# NeoSevenSegment.net
KiCad netlist of a schematic drawn in EAGLE
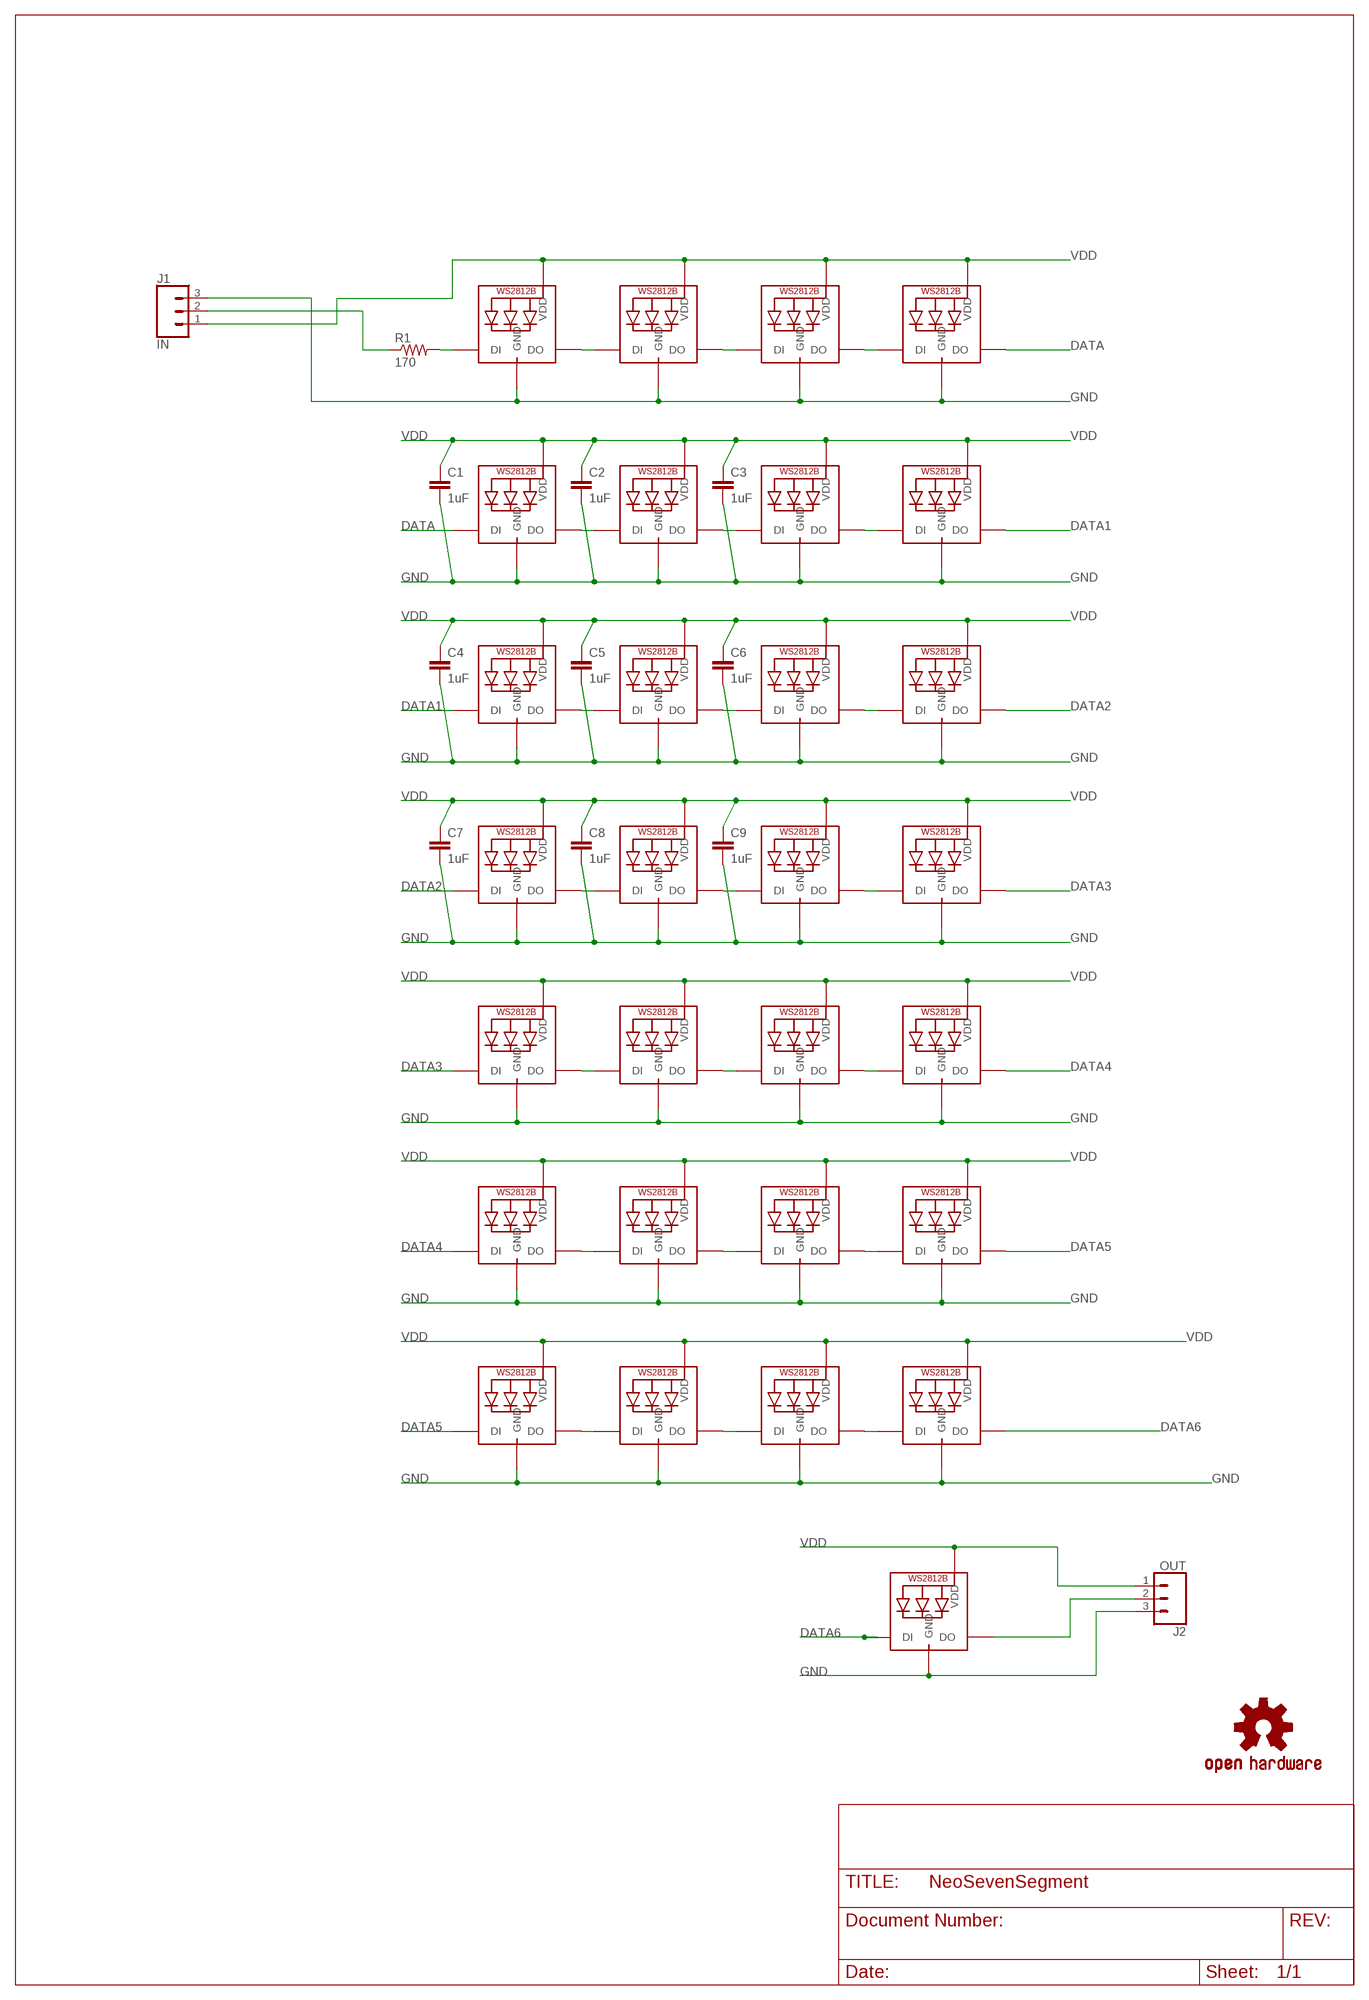
[diagram p0: schematic, sheet 1]

(export (version "E")
  (design (tool "Eeschema 10.0.6"))
  (components
    (comp (ref "C1")
      (value "1uF")
      (footprint "eagle-import:C1210")
      (libsource (lib "eagle-import") (part "C-EUC1210"))
    )
    (comp (ref "C2")
      (value "1uF")
      (footprint "eagle-import:C1210")
      (libsource (lib "eagle-import") (part "C-EUC1210"))
    )
    (comp (ref "C3")
      (value "1uF")
      (footprint "eagle-import:C1210")
      (libsource (lib "eagle-import") (part "C-EUC1210"))
    )
    (comp (ref "C4")
      (value "1uF")
      (footprint "eagle-import:C1210")
      (libsource (lib "eagle-import") (part "C-EUC1210"))
    )
    (comp (ref "C5")
      (value "1uF")
      (footprint "eagle-import:C1210")
      (libsource (lib "eagle-import") (part "C-EUC1210"))
    )
    (comp (ref "C6")
      (value "1uF")
      (footprint "eagle-import:C1210")
      (libsource (lib "eagle-import") (part "C-EUC1210"))
    )
    (comp (ref "C7")
      (value "1uF")
      (footprint "eagle-import:C1210")
      (libsource (lib "eagle-import") (part "C-EUC1210"))
    )
    (comp (ref "C8")
      (value "1uF")
      (footprint "eagle-import:C1210")
      (libsource (lib "eagle-import") (part "C-EUC1210"))
    )
    (comp (ref "C9")
      (value "1uF")
      (footprint "eagle-import:C1210")
      (libsource (lib "eagle-import") (part "C-EUC1210"))
    )
    (comp (ref "J1")
      (value "IN")
      (footprint "eagle-import:1X03_LONGPADS")
      (libsource (lib "eagle-import") (part "CONN_03LONGPADS"))
    )
    (comp (ref "J2")
      (value "OUT")
      (footprint "eagle-import:1X03_LONGPADS")
      (libsource (lib "eagle-import") (part "CONN_03LONGPADS"))
    )
    (comp (ref "LED1")
      (value "WS2812B_5050N")
      (footprint "eagle-import:WS2812B-NARROW")
      (libsource (lib "eagle-import") (part "WS2812B_5050N"))
    )
    (comp (ref "LED2")
      (value "WS2812B_5050N")
      (footprint "eagle-import:WS2812B-NARROW")
      (libsource (lib "eagle-import") (part "WS2812B_5050N"))
    )
    (comp (ref "LED3")
      (value "WS2812B_5050N")
      (footprint "eagle-import:WS2812B-NARROW")
      (libsource (lib "eagle-import") (part "WS2812B_5050N"))
    )
    (comp (ref "LED4")
      (value "WS2812B_5050N")
      (footprint "eagle-import:WS2812B-NARROW")
      (libsource (lib "eagle-import") (part "WS2812B_5050N"))
    )
    (comp (ref "LED5")
      (value "WS2812B_5050N")
      (footprint "eagle-import:WS2812B-NARROW")
      (libsource (lib "eagle-import") (part "WS2812B_5050N"))
    )
    (comp (ref "LED6")
      (value "WS2812B_5050N")
      (footprint "eagle-import:WS2812B-NARROW")
      (libsource (lib "eagle-import") (part "WS2812B_5050N"))
    )
    (comp (ref "LED7")
      (value "WS2812B_5050N")
      (footprint "eagle-import:WS2812B-NARROW")
      (libsource (lib "eagle-import") (part "WS2812B_5050N"))
    )
    (comp (ref "LED8")
      (value "WS2812B_5050N")
      (footprint "eagle-import:WS2812B-NARROW")
      (libsource (lib "eagle-import") (part "WS2812B_5050N"))
    )
    (comp (ref "LED9")
      (value "WS2812B_5050N")
      (footprint "eagle-import:WS2812B-NARROW")
      (libsource (lib "eagle-import") (part "WS2812B_5050N"))
    )
    (comp (ref "LED10")
      (value "WS2812B_5050N")
      (footprint "eagle-import:WS2812B-NARROW")
      (libsource (lib "eagle-import") (part "WS2812B_5050N"))
    )
    (comp (ref "LED11")
      (value "WS2812B_5050N")
      (footprint "eagle-import:WS2812B-NARROW")
      (libsource (lib "eagle-import") (part "WS2812B_5050N"))
    )
    (comp (ref "LED12")
      (value "WS2812B_5050N")
      (footprint "eagle-import:WS2812B-NARROW")
      (libsource (lib "eagle-import") (part "WS2812B_5050N"))
    )
    (comp (ref "LED13")
      (value "WS2812B_5050N")
      (footprint "eagle-import:WS2812B-NARROW")
      (libsource (lib "eagle-import") (part "WS2812B_5050N"))
    )
    (comp (ref "LED14")
      (value "WS2812B_5050N")
      (footprint "eagle-import:WS2812B-NARROW")
      (libsource (lib "eagle-import") (part "WS2812B_5050N"))
    )
    (comp (ref "LED15")
      (value "WS2812B_5050N")
      (footprint "eagle-import:WS2812B-NARROW")
      (libsource (lib "eagle-import") (part "WS2812B_5050N"))
    )
    (comp (ref "LED16")
      (value "WS2812B_5050N")
      (footprint "eagle-import:WS2812B-NARROW")
      (libsource (lib "eagle-import") (part "WS2812B_5050N"))
    )
    (comp (ref "LED17")
      (value "WS2812B_5050N")
      (footprint "eagle-import:WS2812B-NARROW")
      (libsource (lib "eagle-import") (part "WS2812B_5050N"))
    )
    (comp (ref "LED18")
      (value "WS2812B_5050N")
      (footprint "eagle-import:WS2812B-NARROW")
      (libsource (lib "eagle-import") (part "WS2812B_5050N"))
    )
    (comp (ref "LED19")
      (value "WS2812B_5050N")
      (footprint "eagle-import:WS2812B-NARROW")
      (libsource (lib "eagle-import") (part "WS2812B_5050N"))
    )
    (comp (ref "LED20")
      (value "WS2812B_5050N")
      (footprint "eagle-import:WS2812B-NARROW")
      (libsource (lib "eagle-import") (part "WS2812B_5050N"))
    )
    (comp (ref "LED21")
      (value "WS2812B_5050N")
      (footprint "eagle-import:WS2812B-NARROW")
      (libsource (lib "eagle-import") (part "WS2812B_5050N"))
    )
    (comp (ref "LED22")
      (value "WS2812B_5050N")
      (footprint "eagle-import:WS2812B-NARROW")
      (libsource (lib "eagle-import") (part "WS2812B_5050N"))
    )
    (comp (ref "LED23")
      (value "WS2812B_5050N")
      (footprint "eagle-import:WS2812B-NARROW")
      (libsource (lib "eagle-import") (part "WS2812B_5050N"))
    )
    (comp (ref "LED24")
      (value "WS2812B_5050N")
      (footprint "eagle-import:WS2812B-NARROW")
      (libsource (lib "eagle-import") (part "WS2812B_5050N"))
    )
    (comp (ref "LED25")
      (value "WS2812B_5050N")
      (footprint "eagle-import:WS2812B-NARROW")
      (libsource (lib "eagle-import") (part "WS2812B_5050N"))
    )
    (comp (ref "LED26")
      (value "WS2812B_5050N")
      (footprint "eagle-import:WS2812B-NARROW")
      (libsource (lib "eagle-import") (part "WS2812B_5050N"))
    )
    (comp (ref "LED27")
      (value "WS2812B_5050N")
      (footprint "eagle-import:WS2812B-NARROW")
      (libsource (lib "eagle-import") (part "WS2812B_5050N"))
    )
    (comp (ref "LED28")
      (value "WS2812B_5050N")
      (footprint "eagle-import:WS2812B-NARROW")
      (libsource (lib "eagle-import") (part "WS2812B_5050N"))
    )
    (comp (ref "LED29")
      (value "WS2812B_5050N")
      (footprint "eagle-import:WS2812B-NARROW")
      (libsource (lib "eagle-import") (part "WS2812B_5050N"))
    )
    (comp (ref "LOGO1")
      (value "OSHW-LOGOM")
      (footprint "eagle-import:OSHW-LOGO-M")
      (libsource (lib "eagle-import") (part "OSHW-LOGOM"))
    )
    (comp (ref "R1")
      (value "170")
      (footprint "eagle-import:R1206")
      (libsource (lib "eagle-import") (part "R-US_R1206"))
    )
  )
  (nets
    (net (code "1") (name "/DATA") (class "Default")
      (node (ref "LED4") (pin "2-DOUT") (pinfunction "DO_2-DOUT") (pintype "output"))
      (node (ref "LED5") (pin "4-DIN") (pinfunction "DI_4-DIN") (pintype "input"))
    )
    (net (code "2") (name "/DATA1") (class "Default")
      (node (ref "LED8") (pin "2-DOUT") (pinfunction "DO_2-DOUT") (pintype "output"))
      (node (ref "LED9") (pin "4-DIN") (pinfunction "DI_4-DIN") (pintype "input"))
    )
    (net (code "3") (name "/DATA2") (class "Default")
      (node (ref "LED12") (pin "2-DOUT") (pinfunction "DO_2-DOUT") (pintype "output"))
      (node (ref "LED13") (pin "4-DIN") (pinfunction "DI_4-DIN") (pintype "input"))
    )
    (net (code "4") (name "/DATA3") (class "Default")
      (node (ref "LED16") (pin "2-DOUT") (pinfunction "DO_2-DOUT") (pintype "output"))
      (node (ref "LED17") (pin "4-DIN") (pinfunction "DI_4-DIN") (pintype "input"))
    )
    (net (code "5") (name "/DATA4") (class "Default")
      (node (ref "LED20") (pin "2-DOUT") (pinfunction "DO_2-DOUT") (pintype "output"))
      (node (ref "LED21") (pin "4-DIN") (pinfunction "DI_4-DIN") (pintype "input"))
    )
    (net (code "6") (name "/DATA5") (class "Default")
      (node (ref "LED24") (pin "2-DOUT") (pinfunction "DO_2-DOUT") (pintype "output"))
      (node (ref "LED25") (pin "4-DIN") (pinfunction "DI_4-DIN") (pintype "input"))
    )
    (net (code "7") (name "/DATA6") (class "Default")
      (node (ref "LED28") (pin "2-DOUT") (pinfunction "DO_2-DOUT") (pintype "output"))
      (node (ref "LED29") (pin "4-DIN") (pinfunction "DI_4-DIN") (pintype "input"))
    )
    (net (code "8") (name "/GND") (class "Default")
      (node (ref "C1") (pin "2") (pinfunction "2_2") (pintype "passive"))
      (node (ref "C2") (pin "2") (pinfunction "2_2") (pintype "passive"))
      (node (ref "C3") (pin "2") (pinfunction "2_2") (pintype "passive"))
      (node (ref "C4") (pin "2") (pinfunction "2_2") (pintype "passive"))
      (node (ref "C5") (pin "2") (pinfunction "2_2") (pintype "passive"))
      (node (ref "C6") (pin "2") (pinfunction "2_2") (pintype "passive"))
      (node (ref "C7") (pin "2") (pinfunction "2_2") (pintype "passive"))
      (node (ref "C8") (pin "2") (pinfunction "2_2") (pintype "passive"))
      (node (ref "C9") (pin "2") (pinfunction "2_2") (pintype "passive"))
      (node (ref "J1") (pin "3") (pinfunction "3_3") (pintype "passive"))
      (node (ref "J2") (pin "3") (pinfunction "3_3") (pintype "passive"))
      (node (ref "LED1") (pin "3-GND") (pinfunction "GND_3-GND") (pintype "power_in"))
      (node (ref "LED10") (pin "3-GND") (pinfunction "GND_3-GND") (pintype "power_in"))
      (node (ref "LED11") (pin "3-GND") (pinfunction "GND_3-GND") (pintype "power_in"))
      (node (ref "LED12") (pin "3-GND") (pinfunction "GND_3-GND") (pintype "power_in"))
      (node (ref "LED13") (pin "3-GND") (pinfunction "GND_3-GND") (pintype "power_in"))
      (node (ref "LED14") (pin "3-GND") (pinfunction "GND_3-GND") (pintype "power_in"))
      (node (ref "LED15") (pin "3-GND") (pinfunction "GND_3-GND") (pintype "power_in"))
      (node (ref "LED16") (pin "3-GND") (pinfunction "GND_3-GND") (pintype "power_in"))
      (node (ref "LED17") (pin "3-GND") (pinfunction "GND_3-GND") (pintype "power_in"))
      (node (ref "LED18") (pin "3-GND") (pinfunction "GND_3-GND") (pintype "power_in"))
      (node (ref "LED19") (pin "3-GND") (pinfunction "GND_3-GND") (pintype "power_in"))
      (node (ref "LED2") (pin "3-GND") (pinfunction "GND_3-GND") (pintype "power_in"))
      (node (ref "LED20") (pin "3-GND") (pinfunction "GND_3-GND") (pintype "power_in"))
      (node (ref "LED21") (pin "3-GND") (pinfunction "GND_3-GND") (pintype "power_in"))
      (node (ref "LED22") (pin "3-GND") (pinfunction "GND_3-GND") (pintype "power_in"))
      (node (ref "LED23") (pin "3-GND") (pinfunction "GND_3-GND") (pintype "power_in"))
      (node (ref "LED24") (pin "3-GND") (pinfunction "GND_3-GND") (pintype "power_in"))
      (node (ref "LED25") (pin "3-GND") (pinfunction "GND_3-GND") (pintype "power_in"))
      (node (ref "LED26") (pin "3-GND") (pinfunction "GND_3-GND") (pintype "power_in"))
      (node (ref "LED27") (pin "3-GND") (pinfunction "GND_3-GND") (pintype "power_in"))
      (node (ref "LED28") (pin "3-GND") (pinfunction "GND_3-GND") (pintype "power_in"))
      (node (ref "LED29") (pin "3-GND") (pinfunction "GND_3-GND") (pintype "power_in"))
      (node (ref "LED3") (pin "3-GND") (pinfunction "GND_3-GND") (pintype "power_in"))
      (node (ref "LED4") (pin "3-GND") (pinfunction "GND_3-GND") (pintype "power_in"))
      (node (ref "LED5") (pin "3-GND") (pinfunction "GND_3-GND") (pintype "power_in"))
      (node (ref "LED6") (pin "3-GND") (pinfunction "GND_3-GND") (pintype "power_in"))
      (node (ref "LED7") (pin "3-GND") (pinfunction "GND_3-GND") (pintype "power_in"))
      (node (ref "LED8") (pin "3-GND") (pinfunction "GND_3-GND") (pintype "power_in"))
      (node (ref "LED9") (pin "3-GND") (pinfunction "GND_3-GND") (pintype "power_in"))
    )
    (net (code "9") (name "/VDD") (class "Default")
      (node (ref "C1") (pin "1") (pinfunction "1_1") (pintype "passive"))
      (node (ref "C2") (pin "1") (pinfunction "1_1") (pintype "passive"))
      (node (ref "C3") (pin "1") (pinfunction "1_1") (pintype "passive"))
      (node (ref "C4") (pin "1") (pinfunction "1_1") (pintype "passive"))
      (node (ref "C5") (pin "1") (pinfunction "1_1") (pintype "passive"))
      (node (ref "C6") (pin "1") (pinfunction "1_1") (pintype "passive"))
      (node (ref "C7") (pin "1") (pinfunction "1_1") (pintype "passive"))
      (node (ref "C8") (pin "1") (pinfunction "1_1") (pintype "passive"))
      (node (ref "C9") (pin "1") (pinfunction "1_1") (pintype "passive"))
      (node (ref "J1") (pin "1") (pinfunction "1_1") (pintype "passive"))
      (node (ref "J2") (pin "1") (pinfunction "1_1") (pintype "passive"))
      (node (ref "LED1") (pin "1-VDD") (pinfunction "VDD_1-VDD") (pintype "power_in"))
      (node (ref "LED10") (pin "1-VDD") (pinfunction "VDD_1-VDD") (pintype "power_in"))
      (node (ref "LED11") (pin "1-VDD") (pinfunction "VDD_1-VDD") (pintype "power_in"))
      (node (ref "LED12") (pin "1-VDD") (pinfunction "VDD_1-VDD") (pintype "power_in"))
      (node (ref "LED13") (pin "1-VDD") (pinfunction "VDD_1-VDD") (pintype "power_in"))
      (node (ref "LED14") (pin "1-VDD") (pinfunction "VDD_1-VDD") (pintype "power_in"))
      (node (ref "LED15") (pin "1-VDD") (pinfunction "VDD_1-VDD") (pintype "power_in"))
      (node (ref "LED16") (pin "1-VDD") (pinfunction "VDD_1-VDD") (pintype "power_in"))
      (node (ref "LED17") (pin "1-VDD") (pinfunction "VDD_1-VDD") (pintype "power_in"))
      (node (ref "LED18") (pin "1-VDD") (pinfunction "VDD_1-VDD") (pintype "power_in"))
      (node (ref "LED19") (pin "1-VDD") (pinfunction "VDD_1-VDD") (pintype "power_in"))
      (node (ref "LED2") (pin "1-VDD") (pinfunction "VDD_1-VDD") (pintype "power_in"))
      (node (ref "LED20") (pin "1-VDD") (pinfunction "VDD_1-VDD") (pintype "power_in"))
      (node (ref "LED21") (pin "1-VDD") (pinfunction "VDD_1-VDD") (pintype "power_in"))
      (node (ref "LED22") (pin "1-VDD") (pinfunction "VDD_1-VDD") (pintype "power_in"))
      (node (ref "LED23") (pin "1-VDD") (pinfunction "VDD_1-VDD") (pintype "power_in"))
      (node (ref "LED24") (pin "1-VDD") (pinfunction "VDD_1-VDD") (pintype "power_in"))
      (node (ref "LED25") (pin "1-VDD") (pinfunction "VDD_1-VDD") (pintype "power_in"))
      (node (ref "LED26") (pin "1-VDD") (pinfunction "VDD_1-VDD") (pintype "power_in"))
      (node (ref "LED27") (pin "1-VDD") (pinfunction "VDD_1-VDD") (pintype "power_in"))
      (node (ref "LED28") (pin "1-VDD") (pinfunction "VDD_1-VDD") (pintype "power_in"))
      (node (ref "LED29") (pin "1-VDD") (pinfunction "VDD_1-VDD") (pintype "power_in"))
      (node (ref "LED3") (pin "1-VDD") (pinfunction "VDD_1-VDD") (pintype "power_in"))
      (node (ref "LED4") (pin "1-VDD") (pinfunction "VDD_1-VDD") (pintype "power_in"))
      (node (ref "LED5") (pin "1-VDD") (pinfunction "VDD_1-VDD") (pintype "power_in"))
      (node (ref "LED6") (pin "1-VDD") (pinfunction "VDD_1-VDD") (pintype "power_in"))
      (node (ref "LED7") (pin "1-VDD") (pinfunction "VDD_1-VDD") (pintype "power_in"))
      (node (ref "LED8") (pin "1-VDD") (pinfunction "VDD_1-VDD") (pintype "power_in"))
      (node (ref "LED9") (pin "1-VDD") (pinfunction "VDD_1-VDD") (pintype "power_in"))
    )
    (net (code "10") (name "Net-(J1-Pad2)") (class "Default")
      (node (ref "J1") (pin "2") (pinfunction "2_2") (pintype "passive"))
      (node (ref "R1") (pin "1") (pinfunction "1_1") (pintype "passive"))
    )
    (net (code "11") (name "Net-(LED1-DI)") (class "Default")
      (node (ref "LED1") (pin "4-DIN") (pinfunction "DI_4-DIN") (pintype "input"))
      (node (ref "R1") (pin "2") (pinfunction "2_2") (pintype "passive"))
    )
    (net (code "12") (name "Net-(LED1-DO)") (class "Default")
      (node (ref "LED1") (pin "2-DOUT") (pinfunction "DO_2-DOUT") (pintype "output"))
      (node (ref "LED2") (pin "4-DIN") (pinfunction "DI_4-DIN") (pintype "input"))
    )
    (net (code "13") (name "Net-(LED2-DO)") (class "Default")
      (node (ref "LED2") (pin "2-DOUT") (pinfunction "DO_2-DOUT") (pintype "output"))
      (node (ref "LED3") (pin "4-DIN") (pinfunction "DI_4-DIN") (pintype "input"))
    )
    (net (code "14") (name "Net-(LED3-DO)") (class "Default")
      (node (ref "LED3") (pin "2-DOUT") (pinfunction "DO_2-DOUT") (pintype "output"))
      (node (ref "LED4") (pin "4-DIN") (pinfunction "DI_4-DIN") (pintype "input"))
    )
    (net (code "15") (name "Net-(LED5-DO)") (class "Default")
      (node (ref "LED5") (pin "2-DOUT") (pinfunction "DO_2-DOUT") (pintype "output"))
      (node (ref "LED6") (pin "4-DIN") (pinfunction "DI_4-DIN") (pintype "input"))
    )
    (net (code "16") (name "Net-(LED6-DO)") (class "Default")
      (node (ref "LED6") (pin "2-DOUT") (pinfunction "DO_2-DOUT") (pintype "output"))
      (node (ref "LED7") (pin "4-DIN") (pinfunction "DI_4-DIN") (pintype "input"))
    )
    (net (code "17") (name "Net-(LED7-DO)") (class "Default")
      (node (ref "LED7") (pin "2-DOUT") (pinfunction "DO_2-DOUT") (pintype "output"))
      (node (ref "LED8") (pin "4-DIN") (pinfunction "DI_4-DIN") (pintype "input"))
    )
    (net (code "18") (name "Net-(LED10-DI)") (class "Default")
      (node (ref "LED10") (pin "4-DIN") (pinfunction "DI_4-DIN") (pintype "input"))
      (node (ref "LED9") (pin "2-DOUT") (pinfunction "DO_2-DOUT") (pintype "output"))
    )
    (net (code "19") (name "Net-(LED10-DO)") (class "Default")
      (node (ref "LED10") (pin "2-DOUT") (pinfunction "DO_2-DOUT") (pintype "output"))
      (node (ref "LED11") (pin "4-DIN") (pinfunction "DI_4-DIN") (pintype "input"))
    )
    (net (code "20") (name "Net-(LED11-DO)") (class "Default")
      (node (ref "LED11") (pin "2-DOUT") (pinfunction "DO_2-DOUT") (pintype "output"))
      (node (ref "LED12") (pin "4-DIN") (pinfunction "DI_4-DIN") (pintype "input"))
    )
    (net (code "21") (name "Net-(LED13-DO)") (class "Default")
      (node (ref "LED13") (pin "2-DOUT") (pinfunction "DO_2-DOUT") (pintype "output"))
      (node (ref "LED14") (pin "4-DIN") (pinfunction "DI_4-DIN") (pintype "input"))
    )
    (net (code "22") (name "Net-(LED14-DO)") (class "Default")
      (node (ref "LED14") (pin "2-DOUT") (pinfunction "DO_2-DOUT") (pintype "output"))
      (node (ref "LED15") (pin "4-DIN") (pinfunction "DI_4-DIN") (pintype "input"))
    )
    (net (code "23") (name "Net-(LED15-DO)") (class "Default")
      (node (ref "LED15") (pin "2-DOUT") (pinfunction "DO_2-DOUT") (pintype "output"))
      (node (ref "LED16") (pin "4-DIN") (pinfunction "DI_4-DIN") (pintype "input"))
    )
    (net (code "24") (name "Net-(LED17-DO)") (class "Default")
      (node (ref "LED17") (pin "2-DOUT") (pinfunction "DO_2-DOUT") (pintype "output"))
      (node (ref "LED18") (pin "4-DIN") (pinfunction "DI_4-DIN") (pintype "input"))
    )
    (net (code "25") (name "Net-(LED18-DO)") (class "Default")
      (node (ref "LED18") (pin "2-DOUT") (pinfunction "DO_2-DOUT") (pintype "output"))
      (node (ref "LED19") (pin "4-DIN") (pinfunction "DI_4-DIN") (pintype "input"))
    )
    (net (code "26") (name "Net-(LED19-DO)") (class "Default")
      (node (ref "LED19") (pin "2-DOUT") (pinfunction "DO_2-DOUT") (pintype "output"))
      (node (ref "LED20") (pin "4-DIN") (pinfunction "DI_4-DIN") (pintype "input"))
    )
    (net (code "27") (name "Net-(LED21-DO)") (class "Default")
      (node (ref "LED21") (pin "2-DOUT") (pinfunction "DO_2-DOUT") (pintype "output"))
      (node (ref "LED22") (pin "4-DIN") (pinfunction "DI_4-DIN") (pintype "input"))
    )
    (net (code "28") (name "Net-(LED22-DO)") (class "Default")
      (node (ref "LED22") (pin "2-DOUT") (pinfunction "DO_2-DOUT") (pintype "output"))
      (node (ref "LED23") (pin "4-DIN") (pinfunction "DI_4-DIN") (pintype "input"))
    )
    (net (code "29") (name "Net-(LED23-DO)") (class "Default")
      (node (ref "LED23") (pin "2-DOUT") (pinfunction "DO_2-DOUT") (pintype "output"))
      (node (ref "LED24") (pin "4-DIN") (pinfunction "DI_4-DIN") (pintype "input"))
    )
    (net (code "30") (name "Net-(LED25-DO)") (class "Default")
      (node (ref "LED25") (pin "2-DOUT") (pinfunction "DO_2-DOUT") (pintype "output"))
      (node (ref "LED26") (pin "4-DIN") (pinfunction "DI_4-DIN") (pintype "input"))
    )
    (net (code "31") (name "Net-(LED26-DO)") (class "Default")
      (node (ref "LED26") (pin "2-DOUT") (pinfunction "DO_2-DOUT") (pintype "output"))
      (node (ref "LED27") (pin "4-DIN") (pinfunction "DI_4-DIN") (pintype "input"))
    )
    (net (code "32") (name "Net-(LED27-DO)") (class "Default")
      (node (ref "LED27") (pin "2-DOUT") (pinfunction "DO_2-DOUT") (pintype "output"))
      (node (ref "LED28") (pin "4-DIN") (pinfunction "DI_4-DIN") (pintype "input"))
    )
    (net (code "33") (name "Net-(LED29-DO)") (class "Default")
      (node (ref "J2") (pin "2") (pinfunction "2_2") (pintype "passive"))
      (node (ref "LED29") (pin "2-DOUT") (pinfunction "DO_2-DOUT") (pintype "output"))
    )
  )
)
